# Power_ORing.net
KiCad netlist of a schematic drawn in Altium Designer
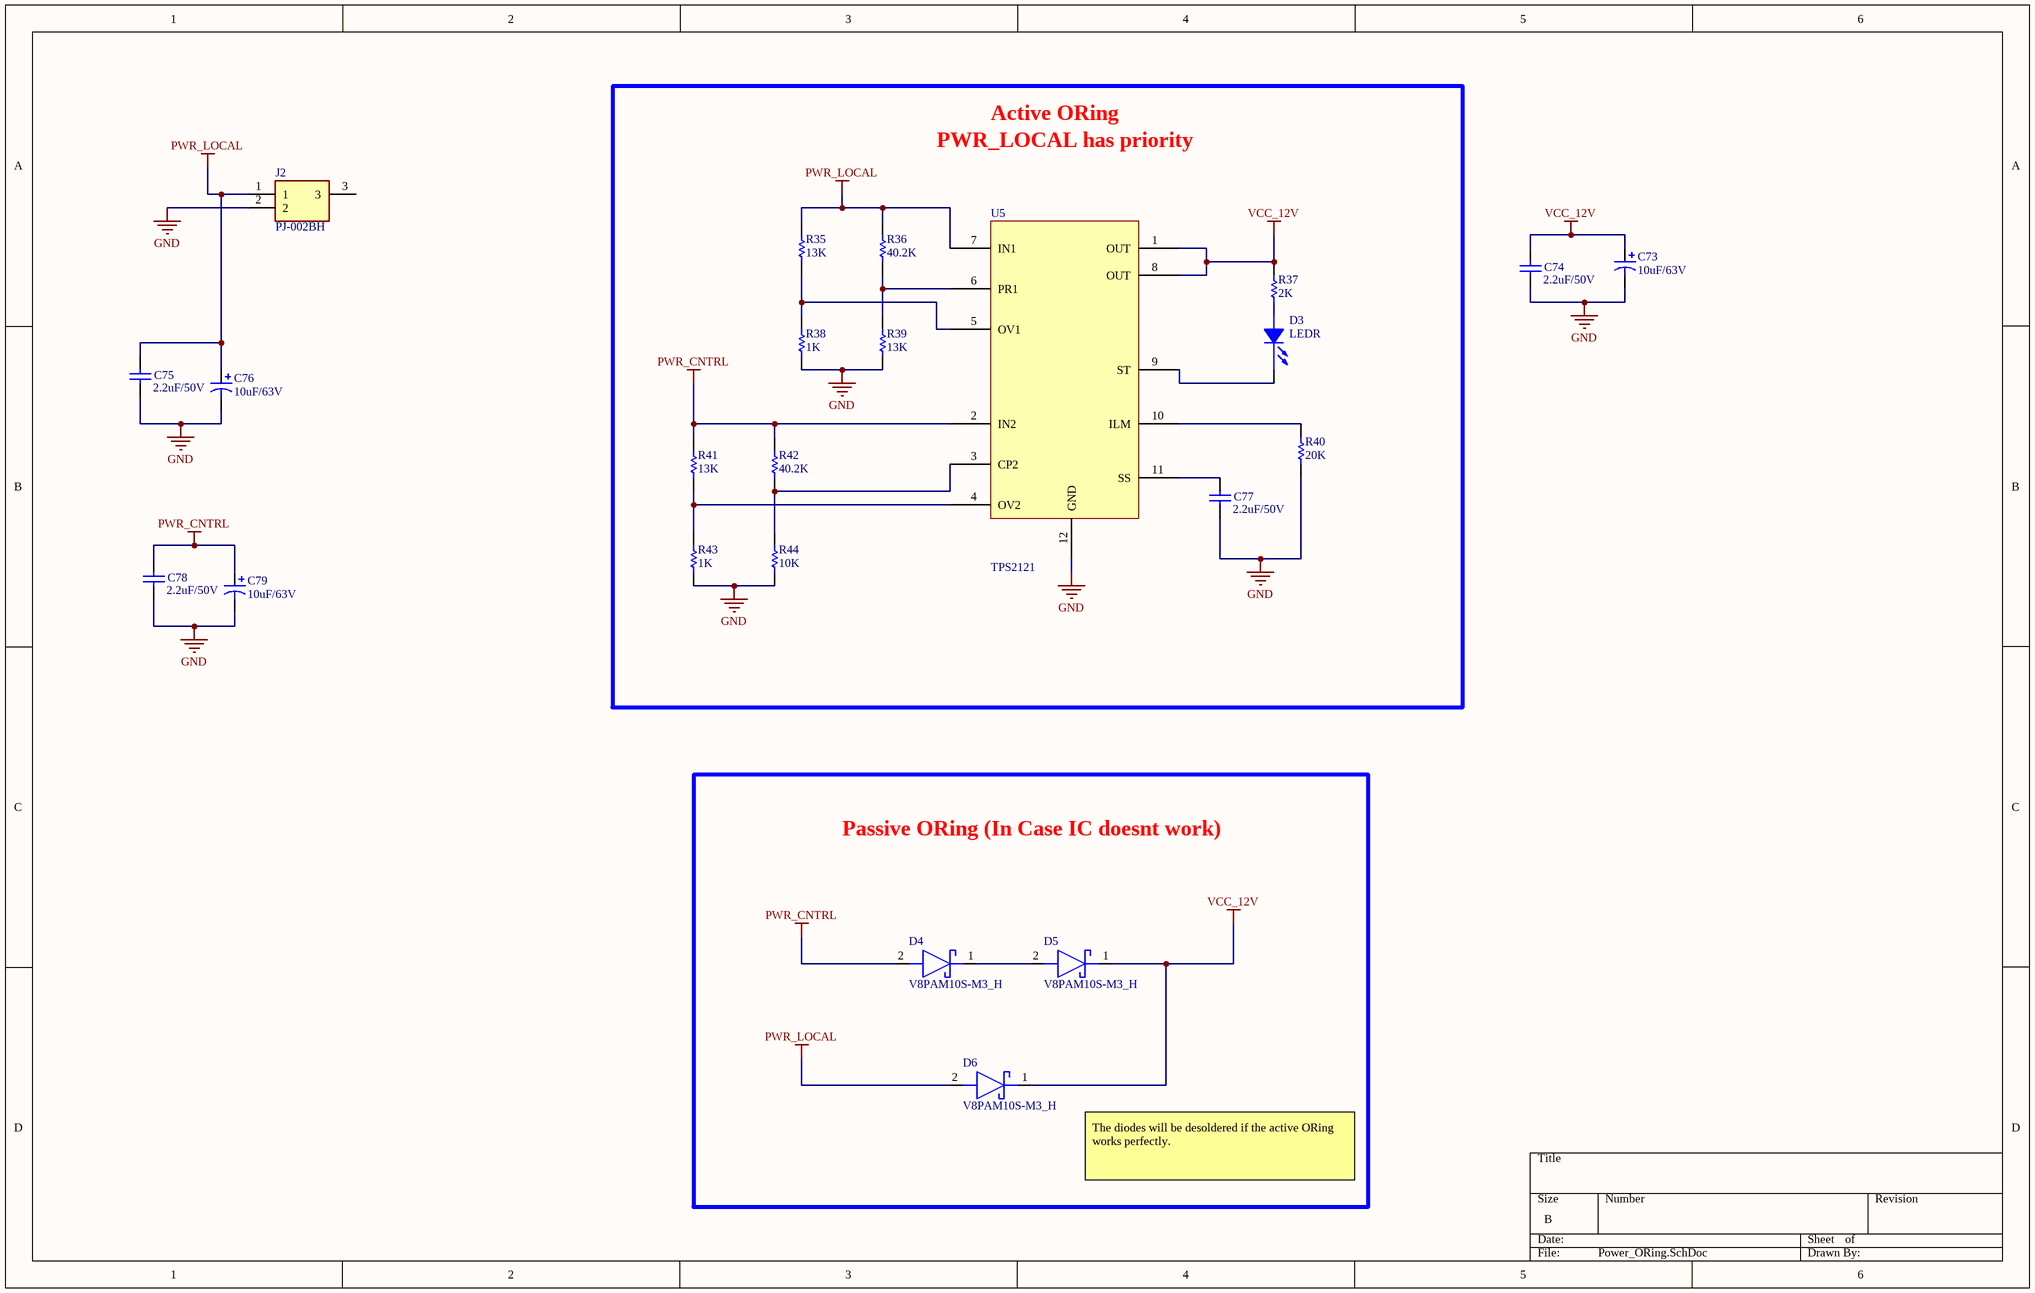
[diagram p0: Power_ORing.SchDoc]

(export (version "E")
  (design (tool "Eeschema 10.0.6"))
  (components
    (comp (ref "C73")
      (value "10uF/63V")
      (footprint "EEE-FN1J100L")
      (description "Polarized Capacitor (Radial)")
      (fields (field (name "MFR") "Panasonic") (field (name "MFR PART NO") "EEE-FN1J100L"))
      (libsource (lib "Miscellaneous Devices") (part "Cap Pol1"))
    )
    (comp (ref "C74")
      (value "2.2uF/50V")
      (footprint "0603C")
      (description "Multilayer Ceramic Capacitors MLCC - SMD/SMT 0603 2.2uF 20% 50VDC X5R")
      (fields (field (name "MFR") "Murata Electronics") (field (name "MFR PART NO") "GRM188R61H225ME11J"))
      (libsource (lib "Miscellaneous Devices") (part "Cap"))
    )
    (comp (ref "C75")
      (value "2.2uF/50V")
      (footprint "0603C")
      (description "Multilayer Ceramic Capacitors MLCC - SMD/SMT 0603 2.2uF 20% 50VDC X5R")
      (fields (field (name "MFR") "Murata Electronics") (field (name "MFR PART NO") "GRM188R61H225ME11J"))
      (libsource (lib "Miscellaneous Devices") (part "Cap"))
    )
    (comp (ref "C76")
      (value "10uF/63V")
      (footprint "EEE-FN1J100L")
      (description "Polarized Capacitor (Radial)")
      (fields (field (name "MFR") "Panasonic") (field (name "MFR PART NO") "EEE-FN1J100L"))
      (libsource (lib "Miscellaneous Devices") (part "Cap Pol1"))
    )
    (comp (ref "C77")
      (value "2.2uF/50V")
      (footprint "0603C")
      (description "Multilayer Ceramic Capacitors MLCC - SMD/SMT 0603 2.2uF 20% 50VDC X5R")
      (fields (field (name "MFR") "Murata Electronics") (field (name "MFR PART NO") "GRM188R61H225ME11J"))
      (libsource (lib "Miscellaneous Devices") (part "Cap"))
    )
    (comp (ref "C78")
      (value "2.2uF/50V")
      (footprint "0603C")
      (description "Multilayer Ceramic Capacitors MLCC - SMD/SMT 0603 2.2uF 20% 50VDC X5R")
      (fields (field (name "MFR") "Murata Electronics") (field (name "MFR PART NO") "GRM188R61H225ME11J"))
      (libsource (lib "Miscellaneous Devices") (part "Cap"))
    )
    (comp (ref "C79")
      (value "10uF/63V")
      (footprint "EEE-FN1J100L")
      (description "Polarized Capacitor (Radial)")
      (fields (field (name "MFR") "Panasonic") (field (name "MFR PART NO") "EEE-FN1J100L"))
      (libsource (lib "Miscellaneous Devices") (part "Cap Pol1"))
    )
    (comp (ref "D3")
      (value "LEDR")
      (footprint "LED_0603")
      (description "Standard LEDs - SMD Red 631nm 14mcd 5mA")
      (fields (field (name "MFR") "Lite-On") (field (name "MFR PART NO") "LTST-C193KRKT-5A"))
      (libsource (lib "de20") (part "LED"))
    )
    (comp (ref "D4")
      (value "V8PAM10S-M3_H")
      (footprint "V8PAM10SHM3H")
      (description "Schottky Diodes & Rectifiers 8A 100V")
      (fields
        (field (name "MFR") "Vishay General Semiconductor")
        (field (name "MFR PART NO") "V8PAM10S-M3/H")
      )
      (libsource (lib "*") (part "V8PAM10S-M3_H"))
    )
    (comp (ref "D5")
      (value "V8PAM10S-M3_H")
      (footprint "V8PAM10SHM3H")
      (description "Schottky Diodes & Rectifiers 8A 100V")
      (fields
        (field (name "MFR") "Vishay General Semiconductor")
        (field (name "MFR PART NO") "V8PAM10S-M3/H")
      )
      (libsource (lib "*") (part "V8PAM10S-M3_H"))
    )
    (comp (ref "D6")
      (value "V8PAM10S-M3_H")
      (footprint "V8PAM10SHM3H")
      (description "Schottky Diodes & Rectifiers 8A 100V")
      (fields
        (field (name "MFR") "Vishay General Semiconductor")
        (field (name "MFR PART NO") "V8PAM10S-M3/H")
      )
      (libsource (lib "*") (part "V8PAM10S-M3_H"))
    )
    (comp (ref "J2")
      (value "PJ-002BH")
      (footprint "ProjCLib:PJ002BH")
      (description "DC Power Connectors Power Jacks")
      (fields (field (name "MFR") "CUI Devices") (field (name "STOCKIEST PART NO") "490-PJ-002BH"))
      (libsource (lib "SamacSys") (part "PJ-002BH"))
    )
    (comp (ref "R35")
      (value "13K")
      (footprint "0603R")
      (description "Thin Film Resistors - SMD 13K ohm 0.1% 25 ppm")
      (fields (field (name "MFR") "KOA Speer") (field (name "MFR PART NO") "RN73R1JTTD1302B25"))
      (libsource (lib "Miscellaneous Devices") (part "Res1"))
    )
    (comp (ref "R36")
      (value "40.2K")
      (footprint "0603R")
      (description "Thick Film Resistors - SMD 0603 Anti-Surge Res. 0.1%, 40.2Koh")
      (fields (field (name "MFR") "Panasonic") (field (name "MFR PART NO") "ERJ-PB3B4022V"))
      (libsource (lib "Miscellaneous Devices") (part "Res1"))
    )
    (comp (ref "R37")
      (value "2K")
      (footprint "0603R")
      (description "Thick Film Resistors - SMD 0603 10Kohms 1% Anti-Sulfur AEC-Q200")
      (fields (field (name "MFR") "ROHM Semiconductor") (field (name "MFR PART NO") "SFR03EZPF1002"))
      (libsource (lib "Miscellaneous Devices") (part "Res1"))
    )
    (comp (ref "R38")
      (value "1K")
      (footprint "0603R")
      (description "Resistor")
      (fields (field (name "MFR") "Vishay / Dale") (field (name "MFR PART NO") "CRCW06031K00FKEAC"))
      (libsource (lib "Miscellaneous Devices") (part "Res1"))
    )
    (comp (ref "R39")
      (value "13K")
      (footprint "0603R")
      (description "Thin Film Resistors - SMD 13K ohm 0.1% 25 ppm")
      (fields (field (name "MFR") "KOA Speer") (field (name "MFR PART NO") "RN73R1JTTD1302B25"))
      (libsource (lib "Miscellaneous Devices") (part "Res1"))
    )
    (comp (ref "R40")
      (value "20K")
      (footprint "0603R")
      (description "Thick Film Resistors - SMD 20K OHM .1% 25PPM")
      (fields (field (name "MFR") "KOA Speer") (field (name "MFR PART NO") "RS73F1JTTD2002B"))
      (libsource (lib "Miscellaneous Devices") (part "Res1"))
    )
    (comp (ref "R41")
      (value "13K")
      (footprint "0603R")
      (description "Thin Film Resistors - SMD 13K ohm 0.1% 25 ppm")
      (fields (field (name "MFR") "KOA Speer") (field (name "MFR PART NO") "RN73R1JTTD1302B25"))
      (libsource (lib "Miscellaneous Devices") (part "Res1"))
    )
    (comp (ref "R42")
      (value "40.2K")
      (footprint "0603R")
      (description "Thick Film Resistors - SMD 0603 Anti-Surge Res. 0.1%, 40.2Koh")
      (fields (field (name "MFR") "Panasonic") (field (name "MFR PART NO") "ERJ-PB3B4022V"))
      (libsource (lib "Miscellaneous Devices") (part "Res1"))
    )
    (comp (ref "R43")
      (value "1K")
      (footprint "0603R")
      (description "Resistor")
      (fields (field (name "MFR") "Vishay / Dale") (field (name "MFR PART NO") "CRCW06031K00FKEAC"))
      (libsource (lib "Miscellaneous Devices") (part "Res1"))
    )
    (comp (ref "R44")
      (value "10K")
      (footprint "0603R")
      (description "Thick Film Resistors - SMD 0603 10Kohms 1% Anti-Sulfur AEC-Q200")
      (fields (field (name "MFR") "ROHM Semiconductor") (field (name "MFR PART NO") "SFR03EZPF1002"))
      (libsource (lib "Miscellaneous Devices") (part "Res1"))
    )
    (comp (ref "U5")
      (value "TPS2121")
      (footprint "TPS2121RUXT")
      (description "Power Switch ICs - Power Distribution")
      (fields (field (name "MFR") "Texas Instruments") (field (name "MFR PART NO") "TPS2121RUXT"))
      (libsource (lib "Schlib1") (part "TPS2121"))
    )
  )
  (nets
    (net (code "1") (name "GND") (class "Default")
      (node (ref "C73") (pin "2") (pinfunction "2_2") (pintype "passive"))
      (node (ref "C74") (pin "1") (pinfunction "1_1") (pintype "passive"))
      (node (ref "C75") (pin "1") (pinfunction "1_1") (pintype "passive"))
      (node (ref "C76") (pin "2") (pinfunction "2_2") (pintype "passive"))
      (node (ref "C77") (pin "1") (pinfunction "1_1") (pintype "passive"))
      (node (ref "C78") (pin "1") (pinfunction "1_1") (pintype "passive"))
      (node (ref "C79") (pin "2") (pinfunction "2_2") (pintype "passive"))
      (node (ref "J2") (pin "2") (pinfunction "2_2") (pintype "passive"))
      (node (ref "R38") (pin "1") (pinfunction "1_1") (pintype "passive"))
      (node (ref "R39") (pin "2") (pinfunction "2_2") (pintype "passive"))
      (node (ref "R40") (pin "2") (pinfunction "2_2") (pintype "passive"))
      (node (ref "R43") (pin "1") (pinfunction "1_1") (pintype "passive"))
      (node (ref "R44") (pin "2") (pinfunction "2_2") (pintype "passive"))
      (node (ref "U5") (pin "12") (pinfunction "GND_12") (pintype "passive"))
    )
    (net (code "2") (name "Net-(D3-ANODE)") (class "Default")
      (node (ref "D3") (pin "1") (pinfunction "ANODE_1") (pintype "passive"))
      (node (ref "R37") (pin "2") (pinfunction "2_2") (pintype "passive"))
    )
    (net (code "3") (name "Net-(D3-CATHODE)") (class "Default")
      (node (ref "D3") (pin "2") (pinfunction "CATHODE_2") (pintype "passive"))
      (node (ref "U5") (pin "9") (pinfunction "ST_9") (pintype "passive"))
    )
    (net (code "4") (name "Net-(D4-K)") (class "Default")
      (node (ref "D4") (pin "1") (pinfunction "K_1") (pintype "passive"))
      (node (ref "D5") (pin "2") (pinfunction "A_2") (pintype "passive"))
    )
    (net (code "5") (name "Net-(U5-CP2)") (class "Default")
      (node (ref "R42") (pin "1") (pinfunction "1_1") (pintype "passive"))
      (node (ref "R44") (pin "1") (pinfunction "1_1") (pintype "passive"))
      (node (ref "U5") (pin "3") (pinfunction "CP2_3") (pintype "passive"))
    )
    (net (code "6") (name "Net-(U5-ILM)") (class "Default")
      (node (ref "R40") (pin "1") (pinfunction "1_1") (pintype "passive"))
      (node (ref "U5") (pin "10") (pinfunction "ILM_10") (pintype "passive"))
    )
    (net (code "7") (name "Net-(U5-OV1)") (class "Default")
      (node (ref "R35") (pin "2") (pinfunction "2_2") (pintype "passive"))
      (node (ref "R38") (pin "2") (pinfunction "2_2") (pintype "passive"))
      (node (ref "U5") (pin "5") (pinfunction "OV1_5") (pintype "passive"))
    )
    (net (code "8") (name "Net-(U5-OV2)") (class "Default")
      (node (ref "R41") (pin "2") (pinfunction "2_2") (pintype "passive"))
      (node (ref "R43") (pin "2") (pinfunction "2_2") (pintype "passive"))
      (node (ref "U5") (pin "4") (pinfunction "OV2_4") (pintype "passive"))
    )
    (net (code "9") (name "Net-(U5-PR1)") (class "Default")
      (node (ref "R36") (pin "1") (pinfunction "1_1") (pintype "passive"))
      (node (ref "R39") (pin "1") (pinfunction "1_1") (pintype "passive"))
      (node (ref "U5") (pin "6") (pinfunction "PR1_6") (pintype "passive"))
    )
    (net (code "10") (name "Net-(U5-SS)") (class "Default")
      (node (ref "C77") (pin "2") (pinfunction "2_2") (pintype "passive"))
      (node (ref "U5") (pin "11") (pinfunction "SS_11") (pintype "passive"))
    )
    (net (code "11") (name "PWR_CNTRL") (class "Default")
      (node (ref "C78") (pin "2") (pinfunction "2_2") (pintype "passive"))
      (node (ref "C79") (pin "1") (pinfunction "1_1") (pintype "passive"))
      (node (ref "D4") (pin "2") (pinfunction "A_2") (pintype "passive"))
      (node (ref "R41") (pin "1") (pinfunction "1_1") (pintype "passive"))
      (node (ref "R42") (pin "2") (pinfunction "2_2") (pintype "passive"))
      (node (ref "U5") (pin "2") (pinfunction "IN2_2") (pintype "passive"))
    )
    (net (code "12") (name "PWR_LOCAL") (class "Default")
      (node (ref "C75") (pin "2") (pinfunction "2_2") (pintype "passive"))
      (node (ref "C76") (pin "1") (pinfunction "1_1") (pintype "passive"))
      (node (ref "D6") (pin "2") (pinfunction "A_2") (pintype "passive"))
      (node (ref "J2") (pin "1") (pinfunction "1_1") (pintype "passive"))
      (node (ref "R35") (pin "1") (pinfunction "1_1") (pintype "passive"))
      (node (ref "R36") (pin "2") (pinfunction "2_2") (pintype "passive"))
      (node (ref "U5") (pin "7") (pinfunction "IN1_7") (pintype "passive"))
    )
    (net (code "13") (name "VCC_12V") (class "Default")
      (node (ref "C73") (pin "1") (pinfunction "1_1") (pintype "passive"))
      (node (ref "C74") (pin "2") (pinfunction "2_2") (pintype "passive"))
      (node (ref "D5") (pin "1") (pinfunction "K_1") (pintype "passive"))
      (node (ref "D6") (pin "1") (pinfunction "K_1") (pintype "passive"))
      (node (ref "R37") (pin "1") (pinfunction "1_1") (pintype "passive"))
      (node (ref "U5") (pin "1") (pinfunction "OUT_1") (pintype "passive"))
      (node (ref "U5") (pin "8") (pinfunction "OUT_8") (pintype "passive"))
    )
    (net (code "14") (name "unconnected-(J2-Pad3)") (class "Default")
      (node (ref "J2") (pin "3") (pinfunction "3_3") (pintype "passive"))
    )
  )
)
